# Sheet1.net
KiCad netlist of a schematic drawn in Altium Designer
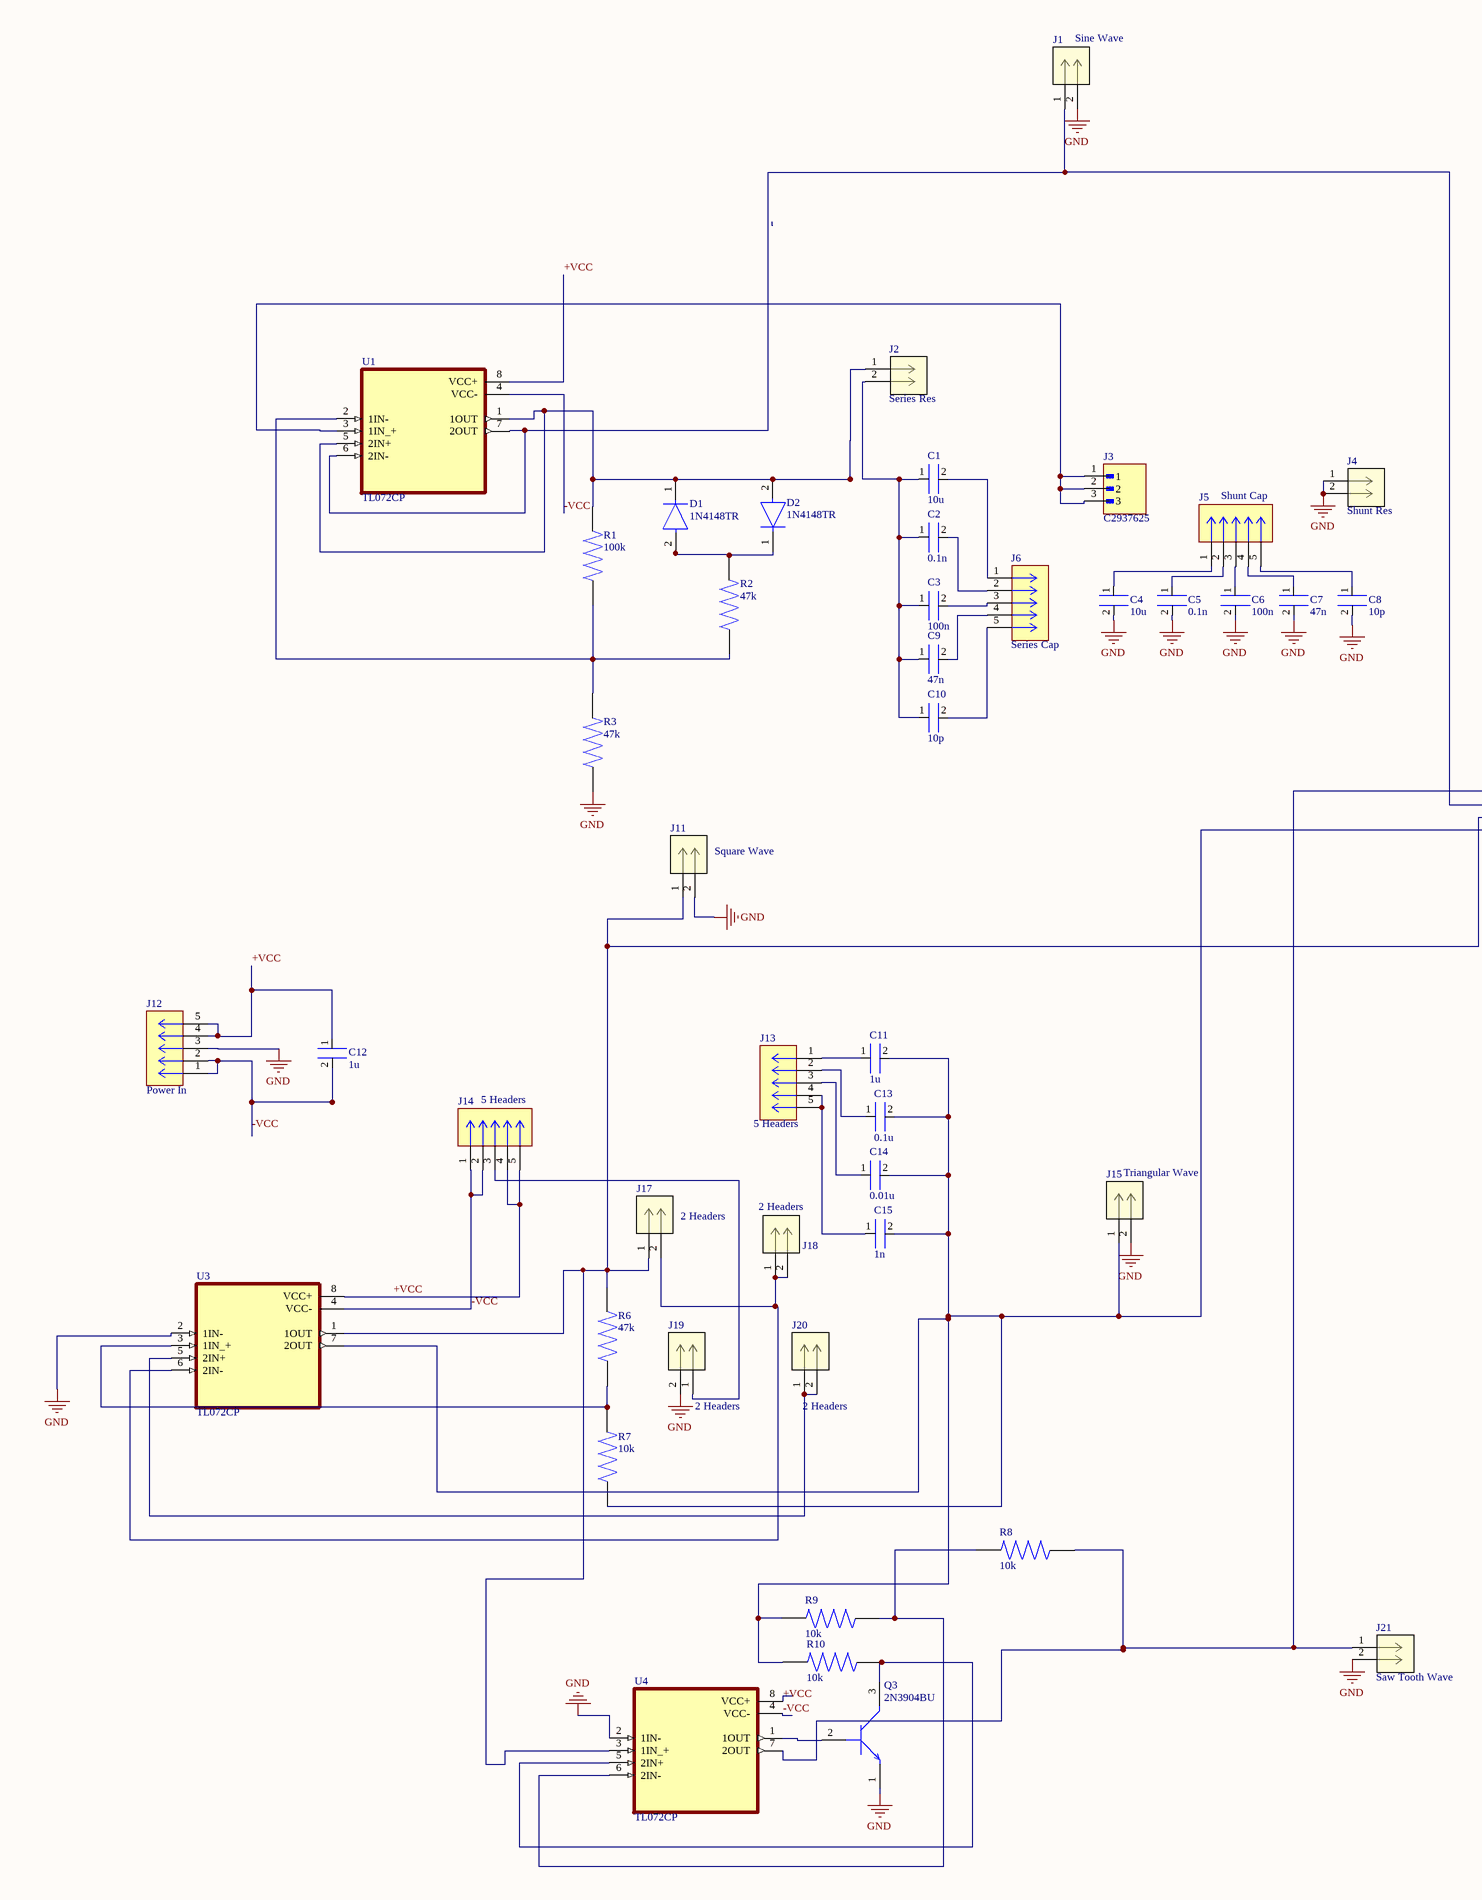
[diagram p0: Sheet1.SchDoc, left]
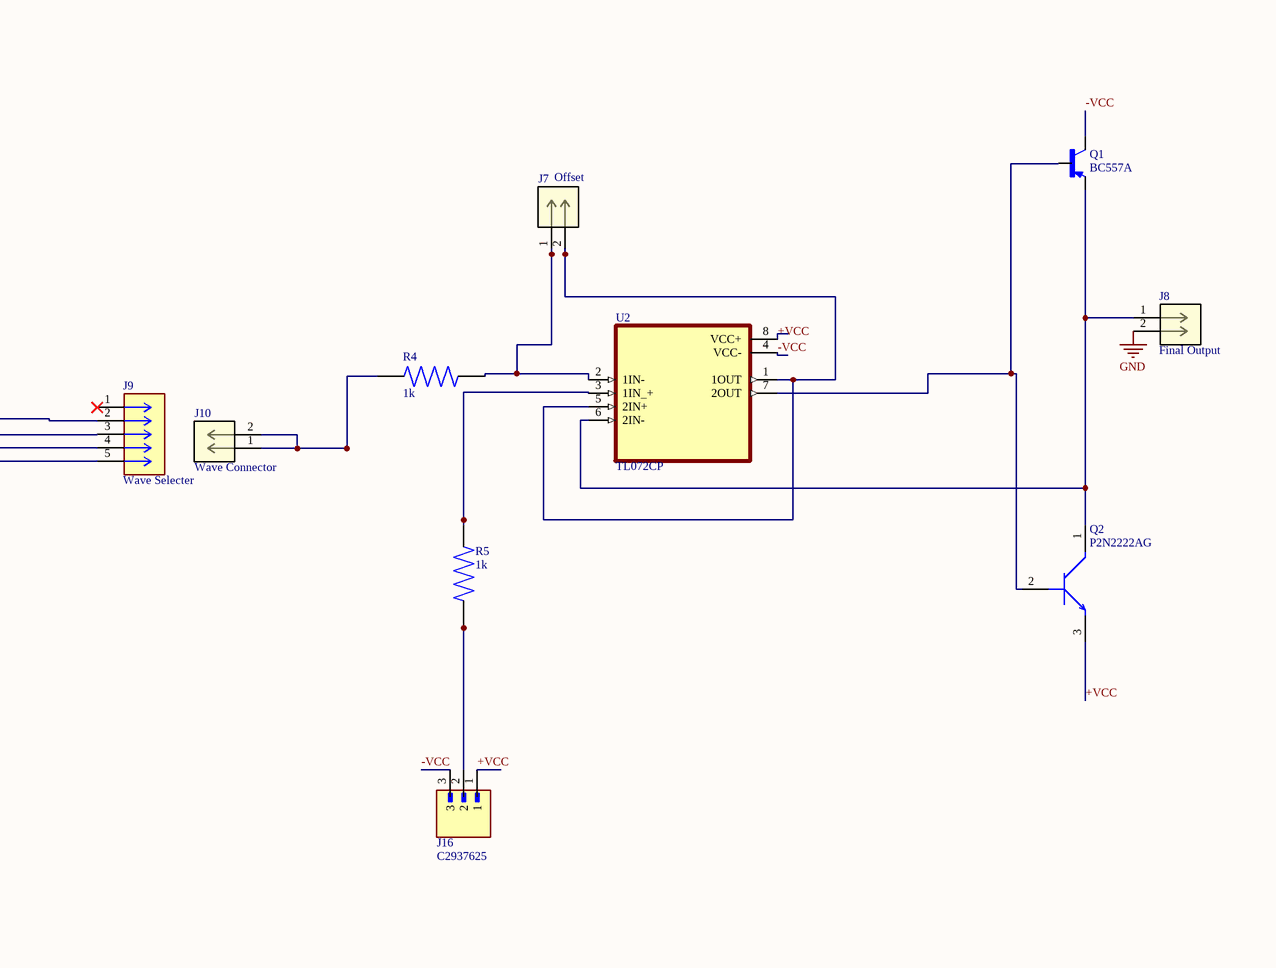
[diagram p1: Sheet1.SchDoc, right]

(export (version "E")
  (design (tool "Eeschema 10.0.6"))
  (components
    (comp (ref "C1")
      (value "10u")
      (footprint "CAPACITORS")
      (description "400V10uF CD110")
      (libsource (lib "Schlib1") (part "CC1206JRNPO9BN100"))
    )
    (comp (ref "C2")
      (value "0.1n")
      (footprint "CAPACITORS")
      (description "USR1H0R1MDD")
      (libsource (lib "Schlib1") (part "CC1206JRNPO9BN100"))
    )
    (comp (ref "C3")
      (value "100n")
      (footprint "CAPACITORS")
      (description "CK45-B3DD102KYNNA")
      (libsource (lib "Schlib1") (part "CC1206JRNPO9BN100"))
    )
    (comp (ref "C4")
      (value "10u")
      (footprint "CAPACITORS")
      (description "400V10uF CD110")
      (libsource (lib "Schlib1") (part "CC1206JRNPO9BN100"))
    )
    (comp (ref "C5")
      (value "0.1n")
      (footprint "CAPACITORS")
      (description "USR1H0R1MDD")
      (libsource (lib "Schlib1") (part "CC1206JRNPO9BN100"))
    )
    (comp (ref "C6")
      (value "100n")
      (footprint "CAPACITORS")
      (description "CK45-B3DD102KYNNA")
      (libsource (lib "Schlib1") (part "CC1206JRNPO9BN100"))
    )
    (comp (ref "C7")
      (value "47n")
      (footprint "CAPACITORS")
      (description "KP473J2J0702")
      (libsource (lib "Schlib1") (part "CC1206JRNPO9BN100"))
    )
    (comp (ref "C8")
      (value "10p")
      (footprint "CAPACITORS")
      (description "CC45SL3FD100JYNNA")
      (libsource (lib "Schlib1") (part "CC1206JRNPO9BN100"))
    )
    (comp (ref "C9")
      (value "47n")
      (footprint "CAPACITORS")
      (description "KP473J2J0702")
      (libsource (lib "Schlib1") (part "CC1206JRNPO9BN100"))
    )
    (comp (ref "C10")
      (value "10p")
      (footprint "CAPACITORS")
      (description "CC45SL3FD100JYNNA")
      (libsource (lib "Schlib1") (part "CC1206JRNPO9BN100"))
    )
    (comp (ref "C11")
      (value "1u")
      (footprint "CAPACITORS")
      (description "PE105J2A0502")
      (libsource (lib "Schlib1") (part "CC1206JRNPO9BN100"))
    )
    (comp (ref "C12")
      (value "1u")
      (footprint "CAPACITORS")
      (description "CC1206KKX7R7BB105")
      (libsource (lib "Schlib1") (part "CC1206JRNPO9BN100"))
    )
    (comp (ref "C13")
      (value "0.1u")
      (footprint "CAPACITORS")
      (description "MPP104J2G10NN22640")
      (libsource (lib "Schlib1") (part "CC1206JRNPO9BN100"))
    )
    (comp (ref "C14")
      (value "0.01u")
      (footprint "CAPACITORS")
      (description "KP103J2G0501")
      (libsource (lib "Schlib1") (part "CC1206JRNPO9BN100"))
    )
    (comp (ref "C15")
      (value "1n")
      (footprint "CAPACITORS")
      (description "CK45-B3DD102KYNNA")
      (libsource (lib "Schlib1") (part "CC1206JRNPO9BN100"))
    )
    (comp (ref "D1")
      (value "1N4148TR")
      (footprint "FP-017AG-MFG")
      (description "DIODE GEN PURP 100V 200MA DO35")
      (fields
        (field (name "OCTOPART") "https://octopart.com/1n4148tr-on+semiconductor-84323125")
        (field (name "MANUFACTURER") "ON Semiconductor")
      )
      (libsource (lib "Altium Content Vault") (part "d7152d700b627762746794eb795d46e"))
    )
    (comp (ref "D2")
      (value "1N4148TR")
      (footprint "FP-017AG-MFG")
      (description "DIODE GEN PURP 100V 200MA DO35")
      (fields
        (field (name "OCTOPART") "https://octopart.com/1n4148tr-on+semiconductor-84323125")
        (field (name "MANUFACTURER") "ON Semiconductor")
      )
      (libsource (lib "Altium Content Vault") (part "d7152d700b627762746794eb795d46e"))
    )
    (comp (ref "J1")
      (value "Sine Wave")
      (footprint "02PIN HEADERS")
      (fields
        (field (name "MANUFACTURER_PART_NUMBER") "22284025")
        (field (name "COPYRIGHT") "Copyright (C) 2025 Ultra Librarian. All rights reserved.")
      )
      (libsource (lib "") (part "22284025_2"))
    )
    (comp (ref "J2")
      (value "Series Res")
      (footprint "02PIN HEADERS")
      (fields
        (field (name "MANUFACTURER_PART_NUMBER") "22284025")
        (field (name "COPYRIGHT") "Copyright (C) 2025 Ultra Librarian. All rights reserved.")
      )
      (libsource (lib "") (part "22284025_4"))
    )
    (comp (ref "J3")
      (value "C2937625")
      (footprint "03PIN HEADERS")
      (fields (field (name "MP") "61300311121"))
      (libsource (lib "") (part "61300311121_1"))
    )
    (comp (ref "J4")
      (value "Shunt Res")
      (footprint "02PIN HEADERS")
      (fields
        (field (name "MANUFACTURER_PART_NUMBER") "22284025")
        (field (name "COPYRIGHT") "Copyright (C) 2025 Ultra Librarian. All rights reserved.")
      )
      (libsource (lib "Schlib1") (part "22284025"))
    )
    (comp (ref "J5")
      (value "Shunt Cap")
      (footprint "05pin Headers")
      (fields (field (name "MP") "22284055"))
      (libsource (lib "Schlib1") (part "22284055"))
    )
    (comp (ref "J6")
      (value "Series Cap")
      (footprint "05pin Headers")
      (fields (field (name "MP") "22284055"))
      (libsource (lib "") (part "22284055_1"))
    )
    (comp (ref "J7")
      (value "Offset")
      (footprint "02PIN HEADERS")
      (fields
        (field (name "MANUFACTURER_PART_NUMBER") "22284025")
        (field (name "COPYRIGHT") "Copyright (C) 2025 Ultra Librarian. All rights reserved.")
      )
      (libsource (lib "") (part "22284025_1"))
    )
    (comp (ref "J8")
      (value "Final Output")
      (footprint "02PIN HEADERS")
      (fields
        (field (name "MANUFACTURER_PART_NUMBER") "22284025")
        (field (name "COPYRIGHT") "Copyright (C) 2025 Ultra Librarian. All rights reserved.")
      )
      (libsource (lib "Schlib1") (part "22284025"))
    )
    (comp (ref "J9")
      (value "Wave Selecter")
      (footprint "05pin Headers")
      (fields (field (name "MP") "22284055"))
      (libsource (lib "") (part "22284055_1"))
    )
    (comp (ref "J10")
      (value "Wave Connector")
      (footprint "02PIN HEADERS")
      (fields
        (field (name "MANUFACTURER_PART_NUMBER") "22284025")
        (field (name "COPYRIGHT") "Copyright (C) 2025 Ultra Librarian. All rights reserved.")
      )
      (libsource (lib "") (part "22284025_3"))
    )
    (comp (ref "J11")
      (value "Square Wave")
      (footprint "02PIN HEADERS")
      (fields
        (field (name "MANUFACTURER_PART_NUMBER") "22284025")
        (field (name "COPYRIGHT") "Copyright (C) 2025 Ultra Librarian. All rights reserved.")
      )
      (libsource (lib "") (part "22284025_2"))
    )
    (comp (ref "J12")
      (value "Power In")
      (footprint "05pin Headers")
      (fields (field (name "MP") "22284055"))
      (libsource (lib "") (part "22284055_2"))
    )
    (comp (ref "J13")
      (value "5 Headers")
      (footprint "05pin Headers")
      (fields (field (name "MP") "22284055"))
      (libsource (lib "") (part "22284055_3"))
    )
    (comp (ref "J14")
      (value "5 Headers")
      (footprint "05pin Headers")
      (fields (field (name "MP") "22284055"))
      (libsource (lib "Schlib1") (part "22284055"))
    )
    (comp (ref "J15")
      (value "Triangular Wave")
      (footprint "02PIN HEADERS")
      (fields
        (field (name "MANUFACTURER_PART_NUMBER") "22284025")
        (field (name "COPYRIGHT") "Copyright (C) 2025 Ultra Librarian. All rights reserved.")
      )
      (libsource (lib "") (part "22284025_2"))
    )
    (comp (ref "J16")
      (value "C2937625")
      (footprint "03PIN HEADERS")
      (fields (field (name "MP") "61300311121"))
      (libsource (lib "Schlib1") (part "61300311121"))
    )
    (comp (ref "J17")
      (value "2 Headers")
      (footprint "02PIN HEADERS")
      (fields
        (field (name "MANUFACTURER_PART_NUMBER") "22284025")
        (field (name "COPYRIGHT") "Copyright (C) 2025 Ultra Librarian. All rights reserved.")
      )
      (libsource (lib "") (part "22284025_2"))
    )
    (comp (ref "J18")
      (value "2 Headers")
      (footprint "02PIN HEADERS")
      (fields
        (field (name "MANUFACTURER_PART_NUMBER") "22284025")
        (field (name "COPYRIGHT") "Copyright (C) 2025 Ultra Librarian. All rights reserved.")
      )
      (libsource (lib "") (part "22284025_2"))
    )
    (comp (ref "J19")
      (value "2 Headers")
      (footprint "02PIN HEADERS")
      (fields
        (field (name "MANUFACTURER_PART_NUMBER") "22284025")
        (field (name "COPYRIGHT") "Copyright (C) 2025 Ultra Librarian. All rights reserved.")
      )
      (libsource (lib "Schlib1") (part "22284025"))
    )
    (comp (ref "J20")
      (value "2 Headers")
      (footprint "02PIN HEADERS")
      (fields
        (field (name "MANUFACTURER_PART_NUMBER") "22284025")
        (field (name "COPYRIGHT") "Copyright (C) 2025 Ultra Librarian. All rights reserved.")
      )
      (libsource (lib "") (part "22284025_2"))
    )
    (comp (ref "J21")
      (value "Saw Tooth Wave")
      (footprint "02PIN HEADERS")
      (fields
        (field (name "MANUFACTURER_PART_NUMBER") "22284025")
        (field (name "COPYRIGHT") "Copyright (C) 2025 Ultra Librarian. All rights reserved.")
      )
      (libsource (lib "Schlib1") (part "22284025"))
    )
    (comp (ref "Q1")
      (value "BC557A")
      (footprint "TO92254P460H750-3")
      (description "BC557ATA")
      (fields (field (name "MF") "Diotec Semiconductor"))
      (libsource (lib "Schlib1") (part "BC557A"))
    )
    (comp (ref "Q2")
      (value "P2N2222AG")
      (footprint "TO92254P460H750-3")
      (libsource (lib "Schlib1") (part "P2N2222AG"))
    )
    (comp (ref "Q3")
      (value "2N3904BU")
      (footprint "TO92254P460H750-3")
      (libsource (lib "Schlib1") (part "2N3904BU"))
    )
    (comp (ref "R1")
      (value "100k")
      (footprint "Resistor")
      (fields (field (name "MP") "RT1206WRD07100KL"))
      (libsource (lib "Schlib1") (part "RT1206WRD07100KL"))
    )
    (comp (ref "R2")
      (value "47k")
      (footprint "Resistor")
      (libsource (lib "Schlib1") (part "RT1206WRD0747KL"))
    )
    (comp (ref "R3")
      (value "47k")
      (footprint "Resistor")
      (libsource (lib "Schlib1") (part "RT1206WRD0747KL"))
    )
    (comp (ref "R4")
      (value "1k")
      (footprint "Resistor")
      (description "ROX1SJ1K0")
      (libsource (lib "Schlib1") (part "RT1206WRD0710KL"))
    )
    (comp (ref "R5")
      (value "1k")
      (footprint "Resistor")
      (description "ROX1SJ1K0")
      (libsource (lib "Schlib1") (part "RT1206WRD0710KL"))
    )
    (comp (ref "R6")
      (value "47k")
      (footprint "Resistor")
      (libsource (lib "Schlib1") (part "RT1206WRD0747KL"))
    )
    (comp (ref "R7")
      (value "10k")
      (footprint "Resistor")
      (libsource (lib "Schlib1") (part "RT1206WRD0710KL"))
    )
    (comp (ref "R8")
      (value "10k")
      (footprint "Resistor")
      (libsource (lib "Schlib1") (part "RT1206WRD0710KL"))
    )
    (comp (ref "R9")
      (value "10k")
      (footprint "Resistor")
      (libsource (lib "Schlib1") (part "RT1206WRD0710KL"))
    )
    (comp (ref "R10")
      (value "10k")
      (footprint "Resistor")
      (libsource (lib "Schlib1") (part "RT1206WRD0710KL"))
    )
    (comp (ref "U1") (value "TL072CP") (footprint "TL072CP") (libsource (lib "Schlib1") (part "TL072CP")))
    (comp (ref "U2") (value "TL072CP") (footprint "TL072CP") (libsource (lib "Schlib1") (part "TL072CP")))
    (comp (ref "U3") (value "TL072CP") (footprint "TL072CP") (libsource (lib "Schlib1") (part "TL072CP")))
    (comp (ref "U4") (value "TL072CP") (footprint "TL072CP") (libsource (lib "Schlib1") (part "TL072CP")))
  )
  (nets
    (net (code "1") (name "/+VCC") (class "Default")
      (node (ref "C12") (pin "1") (pinfunction "1_1") (pintype "passive"))
      (node (ref "J12") (pin "4") (pinfunction "4_4") (pintype "passive"))
      (node (ref "J12") (pin "5") (pinfunction "5_5") (pintype "passive"))
      (node (ref "J14") (pin "4") (pinfunction "4_4") (pintype "passive"))
      (node (ref "J14") (pin "5") (pinfunction "5_5") (pintype "passive"))
      (node (ref "J16") (pin "1") (pinfunction "1_1") (pintype "passive"))
      (node (ref "Q2") (pin "3") (pinfunction "3_3") (pintype "passive"))
      (node (ref "U1") (pin "8") (pinfunction "VCC+_8") (pintype "power_in"))
      (node (ref "U2") (pin "8") (pinfunction "VCC+_8") (pintype "power_in"))
      (node (ref "U3") (pin "8") (pinfunction "VCC+_8") (pintype "power_in"))
      (node (ref "U4") (pin "8") (pinfunction "VCC+_8") (pintype "power_in"))
    )
    (net (code "2") (name "/-VCC") (class "Default")
      (node (ref "C12") (pin "2") (pinfunction "2_2") (pintype "passive"))
      (node (ref "J12") (pin "1") (pinfunction "1_1") (pintype "passive"))
      (node (ref "J12") (pin "2") (pinfunction "2_2") (pintype "passive"))
      (node (ref "J14") (pin "1") (pinfunction "1_1") (pintype "passive"))
      (node (ref "J14") (pin "2") (pinfunction "2_2") (pintype "passive"))
      (node (ref "J16") (pin "3") (pinfunction "3_3") (pintype "passive"))
      (node (ref "Q1") (pin "1") (pinfunction "C_1") (pintype "passive"))
      (node (ref "U1") (pin "4") (pinfunction "VCC-_4") (pintype "power_in"))
      (node (ref "U2") (pin "4") (pinfunction "VCC-_4") (pintype "power_in"))
      (node (ref "U3") (pin "4") (pinfunction "VCC-_4") (pintype "power_in"))
      (node (ref "U4") (pin "4") (pinfunction "VCC-_4") (pintype "power_in"))
    )
    (net (code "3") (name "GND") (class "Default")
      (node (ref "C4") (pin "2") (pinfunction "2_2") (pintype "passive"))
      (node (ref "C5") (pin "2") (pinfunction "2_2") (pintype "passive"))
      (node (ref "C6") (pin "2") (pinfunction "2_2") (pintype "passive"))
      (node (ref "C7") (pin "2") (pinfunction "2_2") (pintype "passive"))
      (node (ref "C8") (pin "2") (pinfunction "2_2") (pintype "passive"))
      (node (ref "J1") (pin "2") (pinfunction "2_2") (pintype "passive"))
      (node (ref "J11") (pin "2") (pinfunction "2_2") (pintype "passive"))
      (node (ref "J12") (pin "3") (pinfunction "3_3") (pintype "passive"))
      (node (ref "J15") (pin "2") (pinfunction "2_2") (pintype "passive"))
      (node (ref "J19") (pin "2") (pinfunction "2_2") (pintype "passive"))
      (node (ref "J21") (pin "2") (pinfunction "2_2") (pintype "passive"))
      (node (ref "J4") (pin "1") (pinfunction "1_1") (pintype "passive"))
      (node (ref "J4") (pin "2") (pinfunction "2_2") (pintype "passive"))
      (node (ref "J8") (pin "2") (pinfunction "2_2") (pintype "passive"))
      (node (ref "Q3") (pin "1") (pinfunction "1_1") (pintype "passive"))
      (node (ref "R3") (pin "1") (pinfunction "1_1") (pintype "passive"))
      (node (ref "U3") (pin "2") (pinfunction "1IN-_2") (pintype "input"))
      (node (ref "U4") (pin "2") (pinfunction "1IN-_2") (pintype "input"))
    )
    (net (code "4") (name "Net-(C1-Pad1)") (class "Default")
      (node (ref "C1") (pin "1") (pinfunction "1_1") (pintype "passive"))
      (node (ref "C10") (pin "1") (pinfunction "1_1") (pintype "passive"))
      (node (ref "C2") (pin "1") (pinfunction "1_1") (pintype "passive"))
      (node (ref "C3") (pin "1") (pinfunction "1_1") (pintype "passive"))
      (node (ref "C9") (pin "1") (pinfunction "1_1") (pintype "passive"))
      (node (ref "J2") (pin "2") (pinfunction "2_2") (pintype "passive"))
    )
    (net (code "5") (name "Net-(C1-Pad2)") (class "Default")
      (node (ref "C1") (pin "2") (pinfunction "2_2") (pintype "passive"))
      (node (ref "J6") (pin "1") (pinfunction "1_1") (pintype "passive"))
    )
    (net (code "6") (name "Net-(C2-Pad2)") (class "Default")
      (node (ref "C2") (pin "2") (pinfunction "2_2") (pintype "passive"))
      (node (ref "J6") (pin "2") (pinfunction "2_2") (pintype "passive"))
    )
    (net (code "7") (name "Net-(C3-Pad2)") (class "Default")
      (node (ref "C3") (pin "2") (pinfunction "2_2") (pintype "passive"))
      (node (ref "J6") (pin "3") (pinfunction "3_3") (pintype "passive"))
    )
    (net (code "8") (name "Net-(C4-Pad1)") (class "Default")
      (node (ref "C4") (pin "1") (pinfunction "1_1") (pintype "passive"))
      (node (ref "J5") (pin "1") (pinfunction "1_1") (pintype "passive"))
    )
    (net (code "9") (name "Net-(C5-Pad1)") (class "Default")
      (node (ref "C5") (pin "1") (pinfunction "1_1") (pintype "passive"))
      (node (ref "J5") (pin "2") (pinfunction "2_2") (pintype "passive"))
    )
    (net (code "10") (name "Net-(C6-Pad1)") (class "Default")
      (node (ref "C6") (pin "1") (pinfunction "1_1") (pintype "passive"))
      (node (ref "J5") (pin "3") (pinfunction "3_3") (pintype "passive"))
    )
    (net (code "11") (name "Net-(C7-Pad1)") (class "Default")
      (node (ref "C7") (pin "1") (pinfunction "1_1") (pintype "passive"))
      (node (ref "J5") (pin "4") (pinfunction "4_4") (pintype "passive"))
    )
    (net (code "12") (name "Net-(C8-Pad1)") (class "Default")
      (node (ref "C8") (pin "1") (pinfunction "1_1") (pintype "passive"))
      (node (ref "J5") (pin "5") (pinfunction "5_5") (pintype "passive"))
    )
    (net (code "13") (name "Net-(C9-Pad2)") (class "Default")
      (node (ref "C9") (pin "2") (pinfunction "2_2") (pintype "passive"))
      (node (ref "J6") (pin "4") (pinfunction "4_4") (pintype "passive"))
    )
    (net (code "14") (name "Net-(C10-Pad2)") (class "Default")
      (node (ref "C10") (pin "2") (pinfunction "2_2") (pintype "passive"))
      (node (ref "J6") (pin "5") (pinfunction "5_5") (pintype "passive"))
    )
    (net (code "15") (name "Net-(C11-Pad1)") (class "Default")
      (node (ref "C11") (pin "1") (pinfunction "1_1") (pintype "passive"))
      (node (ref "J13") (pin "1") (pinfunction "1_1") (pintype "passive"))
    )
    (net (code "16") (name "Net-(C13-Pad1)") (class "Default")
      (node (ref "C13") (pin "1") (pinfunction "1_1") (pintype "passive"))
      (node (ref "J13") (pin "2") (pinfunction "2_2") (pintype "passive"))
    )
    (net (code "17") (name "Net-(C14-Pad1)") (class "Default")
      (node (ref "C14") (pin "1") (pinfunction "1_1") (pintype "passive"))
      (node (ref "J13") (pin "3") (pinfunction "3_3") (pintype "passive"))
    )
    (net (code "18") (name "Net-(C15-Pad1)") (class "Default")
      (node (ref "C15") (pin "1") (pinfunction "1_1") (pintype "passive"))
      (node (ref "J13") (pin "4") (pinfunction "4_4") (pintype "passive"))
      (node (ref "J13") (pin "5") (pinfunction "5_5") (pintype "passive"))
    )
    (net (code "19") (name "Net-(D1-A)") (class "Default")
      (node (ref "D1") (pin "2") (pinfunction "A_2") (pintype "passive"))
      (node (ref "D2") (pin "1") (pinfunction "C_1") (pintype "passive"))
      (node (ref "R2") (pin "2") (pinfunction "2_2") (pintype "passive"))
    )
    (net (code "20") (name "Net-(D1-C)") (class "Default")
      (node (ref "D1") (pin "1") (pinfunction "C_1") (pintype "passive"))
      (node (ref "D2") (pin "2") (pinfunction "A_2") (pintype "passive"))
      (node (ref "J2") (pin "1") (pinfunction "1_1") (pintype "passive"))
      (node (ref "R1") (pin "2") (pinfunction "2_2") (pintype "passive"))
      (node (ref "U1") (pin "1") (pinfunction "1OUT_1") (pintype "output"))
      (node (ref "U1") (pin "5") (pinfunction "2IN+_5") (pintype "input"))
    )
    (net (code "21") (name "Net-(J10-Pad1)") (class "Default")
      (node (ref "J10") (pin "1") (pinfunction "1_1") (pintype "passive"))
      (node (ref "J10") (pin "2") (pinfunction "2_2") (pintype "passive"))
      (node (ref "R4") (pin "1") (pinfunction "1_1") (pintype "passive"))
    )
    (net (code "22") (name "Net-(J14-Pad3)") (class "Default")
      (node (ref "J14") (pin "3") (pinfunction "3_3") (pintype "passive"))
      (node (ref "J19") (pin "1") (pinfunction "1_1") (pintype "passive"))
    )
    (net (code "23") (name "Net-(J16-Pad2)") (class "Default")
      (node (ref "J16") (pin "2") (pinfunction "2_2") (pintype "passive"))
      (node (ref "R5") (pin "2") (pinfunction "2_2") (pintype "passive"))
    )
    (net (code "24") (name "Net-(Q1-B)") (class "Default")
      (node (ref "Q1") (pin "2") (pinfunction "B_2") (pintype "passive"))
      (node (ref "Q2") (pin "2") (pinfunction "2_2") (pintype "passive"))
      (node (ref "U2") (pin "7") (pinfunction "2OUT_7") (pintype "output"))
    )
    (net (code "25") (name "Net-(Q1-E)") (class "Default")
      (node (ref "J8") (pin "1") (pinfunction "1_1") (pintype "passive"))
      (node (ref "Q1") (pin "3") (pinfunction "E_3") (pintype "passive"))
      (node (ref "Q2") (pin "1") (pinfunction "1_1") (pintype "passive"))
      (node (ref "U2") (pin "6") (pinfunction "2IN-_6") (pintype "input"))
    )
    (net (code "26") (name "Net-(U1-1IN-)") (class "Default")
      (node (ref "R1") (pin "1") (pinfunction "1_1") (pintype "passive"))
      (node (ref "R2") (pin "1") (pinfunction "1_1") (pintype "passive"))
      (node (ref "R3") (pin "2") (pinfunction "2_2") (pintype "passive"))
      (node (ref "U1") (pin "2") (pinfunction "1IN-_2") (pintype "input"))
    )
    (net (code "27") (name "Net-(U1-1IN_+)") (class "Default")
      (node (ref "J3") (pin "1") (pinfunction "1_1") (pintype "passive"))
      (node (ref "J3") (pin "2") (pinfunction "2_2") (pintype "passive"))
      (node (ref "J3") (pin "3") (pinfunction "3_3") (pintype "passive"))
      (node (ref "U1") (pin "3") (pinfunction "1IN_+_3") (pintype "input"))
    )
    (net (code "28") (name "Net-(U1-2IN-)") (class "Default")
      (node (ref "J1") (pin "1") (pinfunction "1_1") (pintype "passive"))
      (node (ref "J9") (pin "3") (pinfunction "3_3") (pintype "passive"))
      (node (ref "U1") (pin "6") (pinfunction "2IN-_6") (pintype "input"))
    )
    (net (code "29") (name "Net-(U2-1IN-)") (class "Default")
      (node (ref "J7") (pin "1") (pinfunction "1_1") (pintype "passive"))
      (node (ref "R4") (pin "2") (pinfunction "2_2") (pintype "passive"))
      (node (ref "U2") (pin "2") (pinfunction "1IN-_2") (pintype "input"))
    )
    (net (code "30") (name "Net-(U2-1IN_+)") (class "Default")
      (node (ref "R5") (pin "1") (pinfunction "1_1") (pintype "passive"))
      (node (ref "U2") (pin "3") (pinfunction "1IN_+_3") (pintype "input"))
    )
    (net (code "31") (name "Net-(U2-1OUT)") (class "Default")
      (node (ref "J7") (pin "2") (pinfunction "2_2") (pintype "passive"))
      (node (ref "U2") (pin "1") (pinfunction "1OUT_1") (pintype "output"))
      (node (ref "U2") (pin "5") (pinfunction "2IN+_5") (pintype "input"))
    )
    (net (code "32") (name "Net-(U3-1IN_+)") (class "Default")
      (node (ref "R6") (pin "1") (pinfunction "1_1") (pintype "passive"))
      (node (ref "R7") (pin "2") (pinfunction "2_2") (pintype "passive"))
      (node (ref "U3") (pin "3") (pinfunction "1IN_+_3") (pintype "input"))
    )
    (net (code "33") (name "Net-(U3-1OUT)") (class "Default")
      (node (ref "J11") (pin "1") (pinfunction "1_1") (pintype "passive"))
      (node (ref "J17") (pin "1") (pinfunction "1_1") (pintype "passive"))
      (node (ref "J9") (pin "4") (pinfunction "4_4") (pintype "passive"))
      (node (ref "R6") (pin "2") (pinfunction "2_2") (pintype "passive"))
      (node (ref "U3") (pin "1") (pinfunction "1OUT_1") (pintype "output"))
      (node (ref "U4") (pin "3") (pinfunction "1IN_+_3") (pintype "input"))
    )
    (net (code "34") (name "Net-(U3-2IN+)") (class "Default")
      (node (ref "J20") (pin "1") (pinfunction "1_1") (pintype "passive"))
      (node (ref "J20") (pin "2") (pinfunction "2_2") (pintype "passive"))
      (node (ref "U3") (pin "5") (pinfunction "2IN+_5") (pintype "input"))
    )
    (net (code "35") (name "Net-(U3-2IN-)") (class "Default")
      (node (ref "J17") (pin "2") (pinfunction "2_2") (pintype "passive"))
      (node (ref "J18") (pin "1") (pinfunction "1_1") (pintype "passive"))
      (node (ref "J18") (pin "2") (pinfunction "2_2") (pintype "passive"))
      (node (ref "U3") (pin "6") (pinfunction "2IN-_6") (pintype "input"))
    )
    (net (code "36") (name "Net-(U3-2OUT)") (class "Default")
      (node (ref "C11") (pin "2") (pinfunction "2_2") (pintype "passive"))
      (node (ref "C13") (pin "2") (pinfunction "2_2") (pintype "passive"))
      (node (ref "C14") (pin "2") (pinfunction "2_2") (pintype "passive"))
      (node (ref "C15") (pin "2") (pinfunction "2_2") (pintype "passive"))
      (node (ref "J15") (pin "1") (pinfunction "1_1") (pintype "passive"))
      (node (ref "J9") (pin "5") (pinfunction "5_5") (pintype "passive"))
      (node (ref "R10") (pin "2") (pinfunction "2_2") (pintype "passive"))
      (node (ref "R7") (pin "1") (pinfunction "1_1") (pintype "passive"))
      (node (ref "R9") (pin "2") (pinfunction "2_2") (pintype "passive"))
      (node (ref "U3") (pin "7") (pinfunction "2OUT_7") (pintype "output"))
    )
    (net (code "37") (name "Net-(U4-1OUT)") (class "Default")
      (node (ref "Q3") (pin "2") (pinfunction "2_2") (pintype "passive"))
      (node (ref "U4") (pin "1") (pinfunction "1OUT_1") (pintype "output"))
    )
    (net (code "38") (name "Net-(U4-2IN+)") (class "Default")
      (node (ref "Q3") (pin "3") (pinfunction "3_3") (pintype "passive"))
      (node (ref "R10") (pin "1") (pinfunction "1_1") (pintype "passive"))
      (node (ref "U4") (pin "5") (pinfunction "2IN+_5") (pintype "input"))
    )
    (net (code "39") (name "Net-(U4-2IN-)") (class "Default")
      (node (ref "R8") (pin "2") (pinfunction "2_2") (pintype "passive"))
      (node (ref "R9") (pin "1") (pinfunction "1_1") (pintype "passive"))
      (node (ref "U4") (pin "6") (pinfunction "2IN-_6") (pintype "input"))
    )
    (net (code "40") (name "Net-(U4-2OUT)") (class "Default")
      (node (ref "J21") (pin "1") (pinfunction "1_1") (pintype "passive"))
      (node (ref "J9") (pin "2") (pinfunction "2_2") (pintype "passive"))
      (node (ref "R8") (pin "1") (pinfunction "1_1") (pintype "passive"))
      (node (ref "U4") (pin "7") (pinfunction "2OUT_7") (pintype "output"))
    )
    (net (code "41") (name "unconnected-(J9-Pad1)") (class "Default")
      (node (ref "J9") (pin "1") (pinfunction "1_1") (pintype "passive+no_connect"))
    )
    (net (code "42") (name "unconnected-(U1-2OUT-Pad7)") (class "Default")
      (node (ref "U1") (pin "7") (pinfunction "2OUT_7") (pintype "output"))
    )
  )
)
